# PiGarage.net
KiCad netlist of a schematic drawn in EAGLE
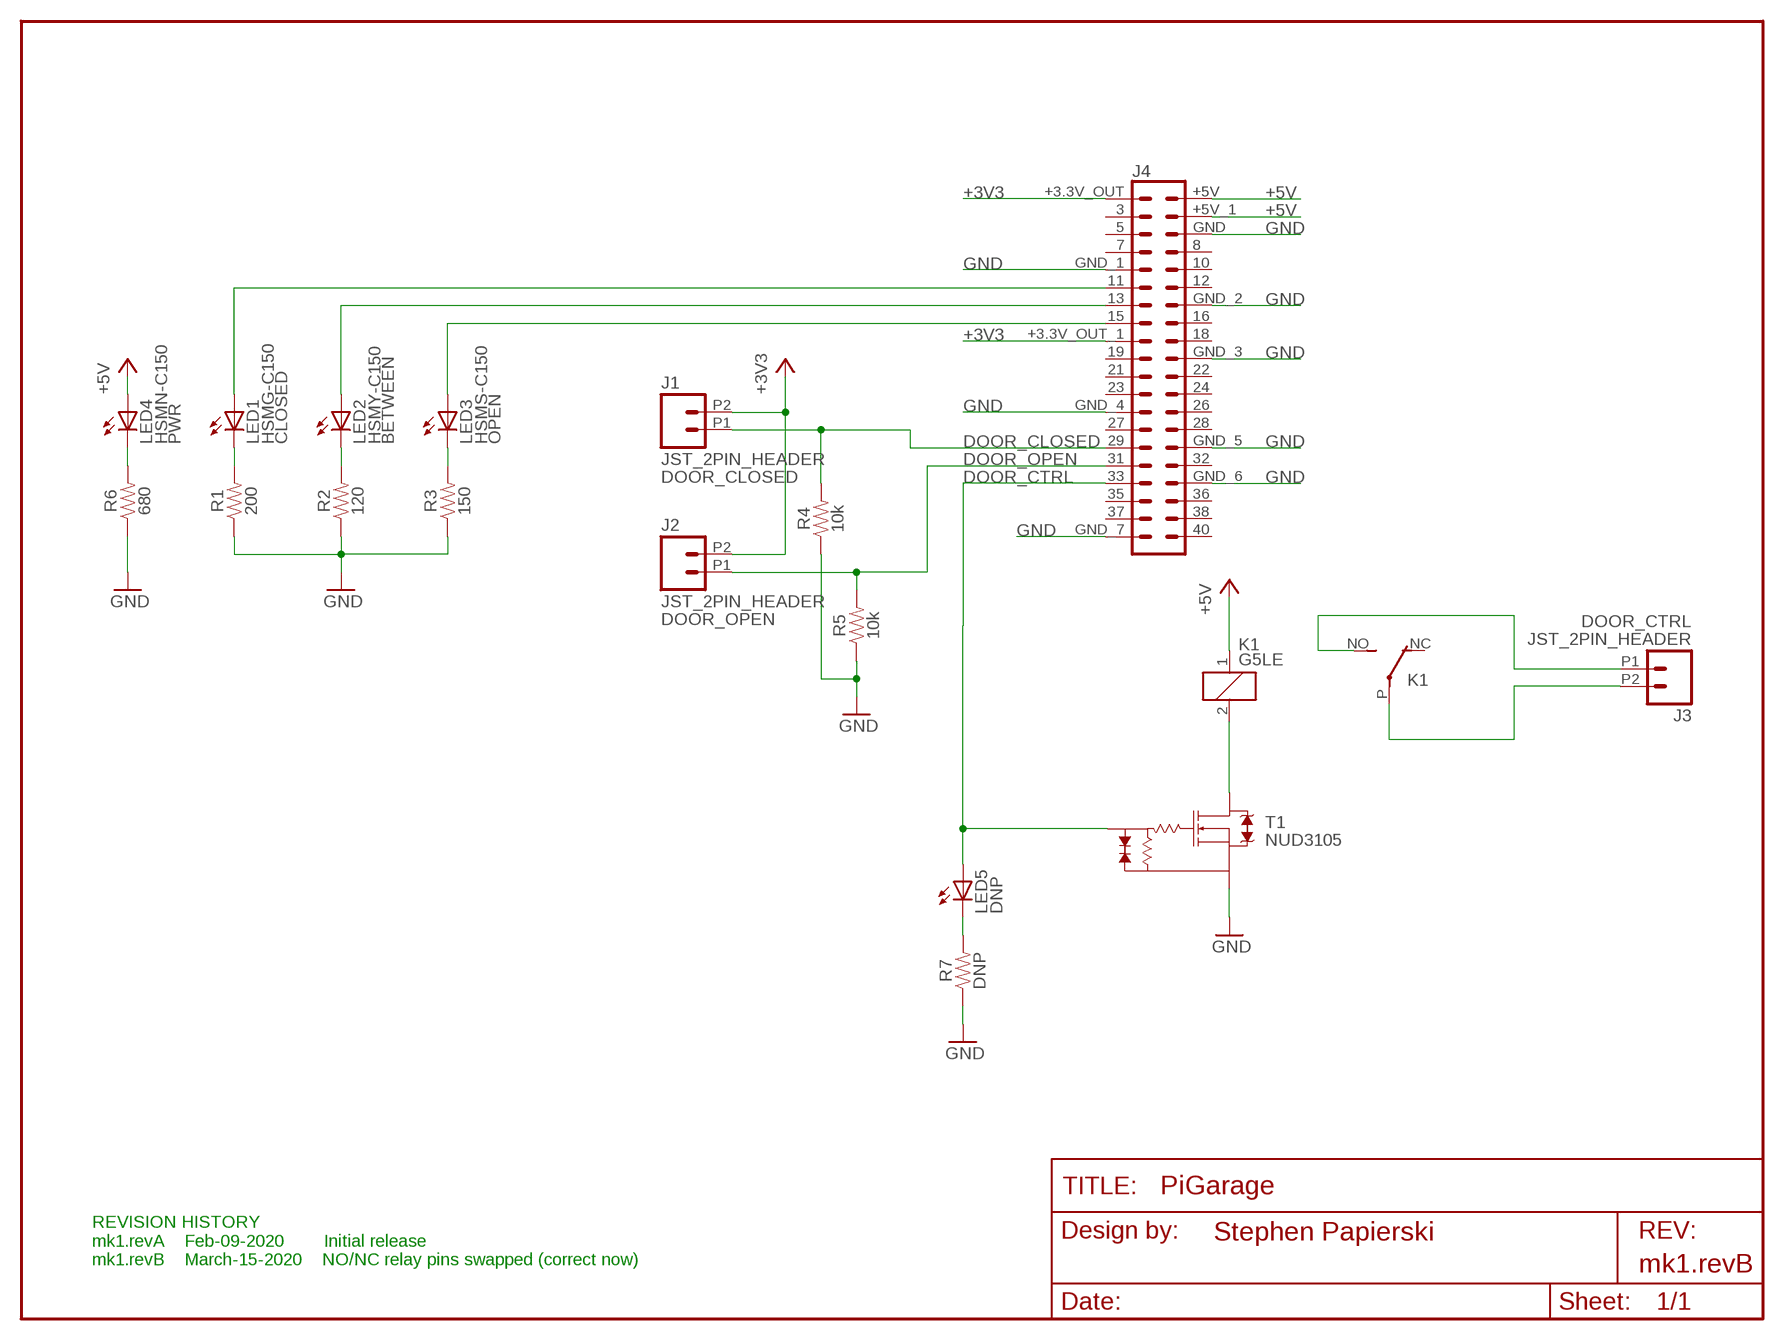
[diagram p0: schematic, sheet 1]

(export (version "E")
  (design (tool "Eeschema 10.0.6"))
  (components
    (comp (ref "FRAME1")
      (value "FRAME-LETTERNO_PACKAGE")
      (footprint "eagle-import:DUMMY")
      (fields
        (field (name "DESIGNER") "Nobody")
        (field (name "REV") "v01")
        (field (name "DESIGNER_1") "Stephen Papierski")
        (field (name "REV_1") "mk1.revB")
      )
      (libsource (lib "eagle-import") (part "FRAME-LETTERNO_PACKAGE"))
    )
    (comp (ref "J1")
      (value "JST_2PIN_HEADER")
      (footprint "eagle-import:JST_2PIN_RIGHT_HEADER")
      (libsource (lib "eagle-import") (part "JST_2PIN_HEADER"))
    )
    (comp (ref "J2")
      (value "JST_2PIN_HEADER")
      (footprint "eagle-import:JST_2PIN_RIGHT_HEADER")
      (libsource (lib "eagle-import") (part "JST_2PIN_HEADER"))
    )
    (comp (ref "J3")
      (value "JST_2PIN_HEADER")
      (footprint "eagle-import:JST_2PIN_RIGHT_HEADER")
      (libsource (lib "eagle-import") (part "JST_2PIN_HEADER"))
    )
    (comp (ref "J4")
      (value "RPI-GPIO-20X2")
      (footprint "eagle-import:RPI-GPIO-20X2")
      (libsource (lib "eagle-import") (part "RPI-GPIO-20X2"))
    )
    (comp (ref "K1")
      (value "G5LE")
      (footprint "eagle-import:G5LE")
      (libsource (lib "eagle-import") (part "G5LE"))
    )
    (comp (ref "LED1")
      (value "HSMG-C150")
      (footprint "eagle-import:CHIPLED_1206")
      (libsource (lib "eagle-import") (part "LEDCHIPLED_1206"))
    )
    (comp (ref "LED2")
      (value "HSMY-C150")
      (footprint "eagle-import:CHIPLED_1206")
      (libsource (lib "eagle-import") (part "LEDCHIPLED_1206"))
    )
    (comp (ref "LED3")
      (value "HSMS-C150")
      (footprint "eagle-import:CHIPLED_1206")
      (libsource (lib "eagle-import") (part "LEDCHIPLED_1206"))
    )
    (comp (ref "LED4")
      (value "HSMN-C150")
      (footprint "eagle-import:CHIPLED_1206")
      (libsource (lib "eagle-import") (part "LEDCHIPLED_1206"))
    )
    (comp (ref "LED5")
      (value "DNP")
      (footprint "eagle-import:CHIPLED_1206")
      (libsource (lib "eagle-import") (part "LEDCHIPLED_1206"))
    )
    (comp (ref "R1")
      (value "200")
      (footprint "eagle-import:0805")
      (libsource (lib "eagle-import") (part "RESISTOR0805"))
    )
    (comp (ref "R2")
      (value "120")
      (footprint "eagle-import:0805")
      (libsource (lib "eagle-import") (part "RESISTOR0805"))
    )
    (comp (ref "R3")
      (value "150")
      (footprint "eagle-import:0805")
      (libsource (lib "eagle-import") (part "RESISTOR0805"))
    )
    (comp (ref "R4")
      (value "10k")
      (footprint "eagle-import:0805")
      (libsource (lib "eagle-import") (part "RESISTOR0805"))
    )
    (comp (ref "R5")
      (value "10k")
      (footprint "eagle-import:0805")
      (libsource (lib "eagle-import") (part "RESISTOR0805"))
    )
    (comp (ref "R6")
      (value "680")
      (footprint "eagle-import:0805")
      (libsource (lib "eagle-import") (part "RESISTOR0805"))
    )
    (comp (ref "R7")
      (value "DNP")
      (footprint "eagle-import:0805")
      (libsource (lib "eagle-import") (part "RESISTOR0805"))
    )
    (comp (ref "T1")
      (value "NUD3105")
      (footprint "eagle-import:SOT23")
      (libsource (lib "eagle-import") (part "NUD3105"))
    )
  )
  (nets
    (net (code "1") (name "+3V3") (class "Default")
      (node (ref "J1") (pin "P2") (pinfunction "2_P2") (pintype "passive"))
      (node (ref "J2") (pin "P2") (pinfunction "2_P2") (pintype "passive"))
      (node (ref "J4") (pin "+3.3V_OUT") (pinfunction "1_+3.3V_OUT") (pintype "passive"))
      (node (ref "J4") (pin "+3.3V_OUT_1") (pinfunction "17_+3.3V_OUT_1") (pintype "passive"))
    )
    (net (code "2") (name "+5V") (class "Default")
      (node (ref "J4") (pin "+5V") (pinfunction "2_+5V") (pintype "passive"))
      (node (ref "J4") (pin "+5V_1") (pinfunction "4_+5V_1") (pintype "passive"))
      (node (ref "K1") (pin "1") (pinfunction "1_1") (pintype "passive"))
      (node (ref "LED4") (pin "A") (pinfunction "A_A") (pintype "passive"))
    )
    (net (code "3") (name "/DOOR_CLOSED") (class "Default")
      (node (ref "J1") (pin "P1") (pinfunction "1_P1") (pintype "passive"))
      (node (ref "J4") (pin "29") (pinfunction "29_29") (pintype "passive"))
      (node (ref "R4") (pin "2") (pinfunction "2_2") (pintype "passive"))
    )
    (net (code "4") (name "/DOOR_CTRL") (class "Default")
      (node (ref "J4") (pin "33") (pinfunction "33_33") (pintype "passive"))
      (node (ref "LED5") (pin "A") (pinfunction "A_A") (pintype "passive"))
      (node (ref "T1") (pin "1") (pinfunction "G_1") (pintype "bidirectional"))
    )
    (net (code "5") (name "/DOOR_OPEN") (class "Default")
      (node (ref "J2") (pin "P1") (pinfunction "1_P1") (pintype "passive"))
      (node (ref "J4") (pin "31") (pinfunction "31_31") (pintype "passive"))
      (node (ref "R5") (pin "2") (pinfunction "2_2") (pintype "passive"))
    )
    (net (code "6") (name "GND") (class "Default")
      (node (ref "J4") (pin "GND") (pinfunction "6_GND") (pintype "passive"))
      (node (ref "J4") (pin "GND_1") (pinfunction "9_GND_1") (pintype "passive"))
      (node (ref "J4") (pin "GND_2") (pinfunction "14_GND_2") (pintype "passive"))
      (node (ref "J4") (pin "GND_3") (pinfunction "20_GND_3") (pintype "passive"))
      (node (ref "J4") (pin "GND_4") (pinfunction "25_GND_4") (pintype "passive"))
      (node (ref "J4") (pin "GND_5") (pinfunction "30_GND_5") (pintype "passive"))
      (node (ref "J4") (pin "GND_6") (pinfunction "34_GND_6") (pintype "passive"))
      (node (ref "J4") (pin "GND_7") (pinfunction "39_GND_7") (pintype "passive"))
      (node (ref "R1") (pin "1") (pinfunction "1_1") (pintype "passive"))
      (node (ref "R2") (pin "1") (pinfunction "1_1") (pintype "passive"))
      (node (ref "R3") (pin "1") (pinfunction "1_1") (pintype "passive"))
      (node (ref "R4") (pin "1") (pinfunction "1_1") (pintype "passive"))
      (node (ref "R5") (pin "1") (pinfunction "1_1") (pintype "passive"))
      (node (ref "R6") (pin "1") (pinfunction "1_1") (pintype "passive"))
      (node (ref "R7") (pin "1") (pinfunction "1_1") (pintype "passive"))
      (node (ref "T1") (pin "2") (pinfunction "S_2") (pintype "bidirectional"))
    )
    (net (code "7") (name "Net-(J3-1)") (class "Default")
      (node (ref "J3") (pin "P1") (pinfunction "1_P1") (pintype "passive"))
      (node (ref "K1") (pin "NO") (pinfunction "NO_NO") (pintype "passive"))
    )
    (net (code "8") (name "Net-(J3-2)") (class "Default")
      (node (ref "J3") (pin "P2") (pinfunction "2_P2") (pintype "passive"))
      (node (ref "K1") (pin "P") (pinfunction "P_P") (pintype "passive"))
    )
    (net (code "9") (name "Net-(J4-Pad11)") (class "Default")
      (node (ref "J4") (pin "11") (pinfunction "11_11") (pintype "passive"))
      (node (ref "LED1") (pin "A") (pinfunction "A_A") (pintype "passive"))
    )
    (net (code "10") (name "Net-(J4-Pad13)") (class "Default")
      (node (ref "J4") (pin "13") (pinfunction "13_13") (pintype "passive"))
      (node (ref "LED2") (pin "A") (pinfunction "A_A") (pintype "passive"))
    )
    (net (code "11") (name "Net-(J4-Pad15)") (class "Default")
      (node (ref "J4") (pin "15") (pinfunction "15_15") (pintype "passive"))
      (node (ref "LED3") (pin "A") (pinfunction "A_A") (pintype "passive"))
    )
    (net (code "12") (name "Net-(LED1-PadC)") (class "Default")
      (node (ref "LED1") (pin "C") (pinfunction "C_C") (pintype "passive"))
      (node (ref "R1") (pin "2") (pinfunction "2_2") (pintype "passive"))
    )
    (net (code "13") (name "Net-(LED2-PadC)") (class "Default")
      (node (ref "LED2") (pin "C") (pinfunction "C_C") (pintype "passive"))
      (node (ref "R2") (pin "2") (pinfunction "2_2") (pintype "passive"))
    )
    (net (code "14") (name "Net-(LED3-PadC)") (class "Default")
      (node (ref "LED3") (pin "C") (pinfunction "C_C") (pintype "passive"))
      (node (ref "R3") (pin "2") (pinfunction "2_2") (pintype "passive"))
    )
    (net (code "15") (name "Net-(LED4-PadC)") (class "Default")
      (node (ref "LED4") (pin "C") (pinfunction "C_C") (pintype "passive"))
      (node (ref "R6") (pin "2") (pinfunction "2_2") (pintype "passive"))
    )
    (net (code "16") (name "Net-(LED5-PadC)") (class "Default")
      (node (ref "LED5") (pin "C") (pinfunction "C_C") (pintype "passive"))
      (node (ref "R7") (pin "2") (pinfunction "2_2") (pintype "passive"))
    )
    (net (code "17") (name "Net-(T1-D)") (class "Default")
      (node (ref "K1") (pin "2") (pinfunction "2_2") (pintype "passive"))
      (node (ref "T1") (pin "3") (pinfunction "D_3") (pintype "bidirectional"))
    )
    (net (code "18") (name "unconnected-(J4-Pad3)") (class "Default")
      (node (ref "J4") (pin "3") (pinfunction "3_3") (pintype "passive"))
    )
    (net (code "19") (name "unconnected-(J4-Pad5)") (class "Default")
      (node (ref "J4") (pin "5") (pinfunction "5_5") (pintype "passive"))
    )
    (net (code "20") (name "unconnected-(J4-Pad7)") (class "Default")
      (node (ref "J4") (pin "7") (pinfunction "7_7") (pintype "passive"))
    )
    (net (code "21") (name "unconnected-(J4-Pad8)") (class "Default")
      (node (ref "J4") (pin "8") (pinfunction "8_8") (pintype "passive"))
    )
    (net (code "22") (name "unconnected-(J4-Pad10)") (class "Default")
      (node (ref "J4") (pin "10") (pinfunction "10_10") (pintype "passive"))
    )
    (net (code "23") (name "unconnected-(J4-Pad12)") (class "Default")
      (node (ref "J4") (pin "12") (pinfunction "12_12") (pintype "passive"))
    )
    (net (code "24") (name "unconnected-(J4-Pad16)") (class "Default")
      (node (ref "J4") (pin "16") (pinfunction "16_16") (pintype "passive"))
    )
    (net (code "25") (name "unconnected-(J4-Pad18)") (class "Default")
      (node (ref "J4") (pin "18") (pinfunction "18_18") (pintype "passive"))
    )
    (net (code "26") (name "unconnected-(J4-Pad19)") (class "Default")
      (node (ref "J4") (pin "19") (pinfunction "19_19") (pintype "passive"))
    )
    (net (code "27") (name "unconnected-(J4-Pad21)") (class "Default")
      (node (ref "J4") (pin "21") (pinfunction "21_21") (pintype "passive"))
    )
    (net (code "28") (name "unconnected-(J4-Pad22)") (class "Default")
      (node (ref "J4") (pin "22") (pinfunction "22_22") (pintype "passive"))
    )
    (net (code "29") (name "unconnected-(J4-Pad23)") (class "Default")
      (node (ref "J4") (pin "23") (pinfunction "23_23") (pintype "passive"))
    )
    (net (code "30") (name "unconnected-(J4-Pad24)") (class "Default")
      (node (ref "J4") (pin "24") (pinfunction "24_24") (pintype "passive"))
    )
    (net (code "31") (name "unconnected-(J4-Pad26)") (class "Default")
      (node (ref "J4") (pin "26") (pinfunction "26_26") (pintype "passive"))
    )
    (net (code "32") (name "unconnected-(J4-Pad27)") (class "Default")
      (node (ref "J4") (pin "27") (pinfunction "27_27") (pintype "passive"))
    )
    (net (code "33") (name "unconnected-(J4-Pad28)") (class "Default")
      (node (ref "J4") (pin "28") (pinfunction "28_28") (pintype "passive"))
    )
    (net (code "34") (name "unconnected-(J4-Pad32)") (class "Default")
      (node (ref "J4") (pin "32") (pinfunction "32_32") (pintype "passive"))
    )
    (net (code "35") (name "unconnected-(J4-Pad35)") (class "Default")
      (node (ref "J4") (pin "35") (pinfunction "35_35") (pintype "passive"))
    )
    (net (code "36") (name "unconnected-(J4-Pad36)") (class "Default")
      (node (ref "J4") (pin "36") (pinfunction "36_36") (pintype "passive"))
    )
    (net (code "37") (name "unconnected-(J4-Pad37)") (class "Default")
      (node (ref "J4") (pin "37") (pinfunction "37_37") (pintype "passive"))
    )
    (net (code "38") (name "unconnected-(J4-Pad38)") (class "Default")
      (node (ref "J4") (pin "38") (pinfunction "38_38") (pintype "passive"))
    )
    (net (code "39") (name "unconnected-(J4-Pad40)") (class "Default")
      (node (ref "J4") (pin "40") (pinfunction "40_40") (pintype "passive"))
    )
    (net (code "40") (name "unconnected-(K1-PadNC)") (class "Default")
      (node (ref "K1") (pin "NC") (pinfunction "NC_NC") (pintype "passive"))
    )
  )
)
